# SCH_LOWCURRENT_LD293D_DRIVER_2026-05-30.net
KiCad netlist of a schematic drawn in EasyEDA
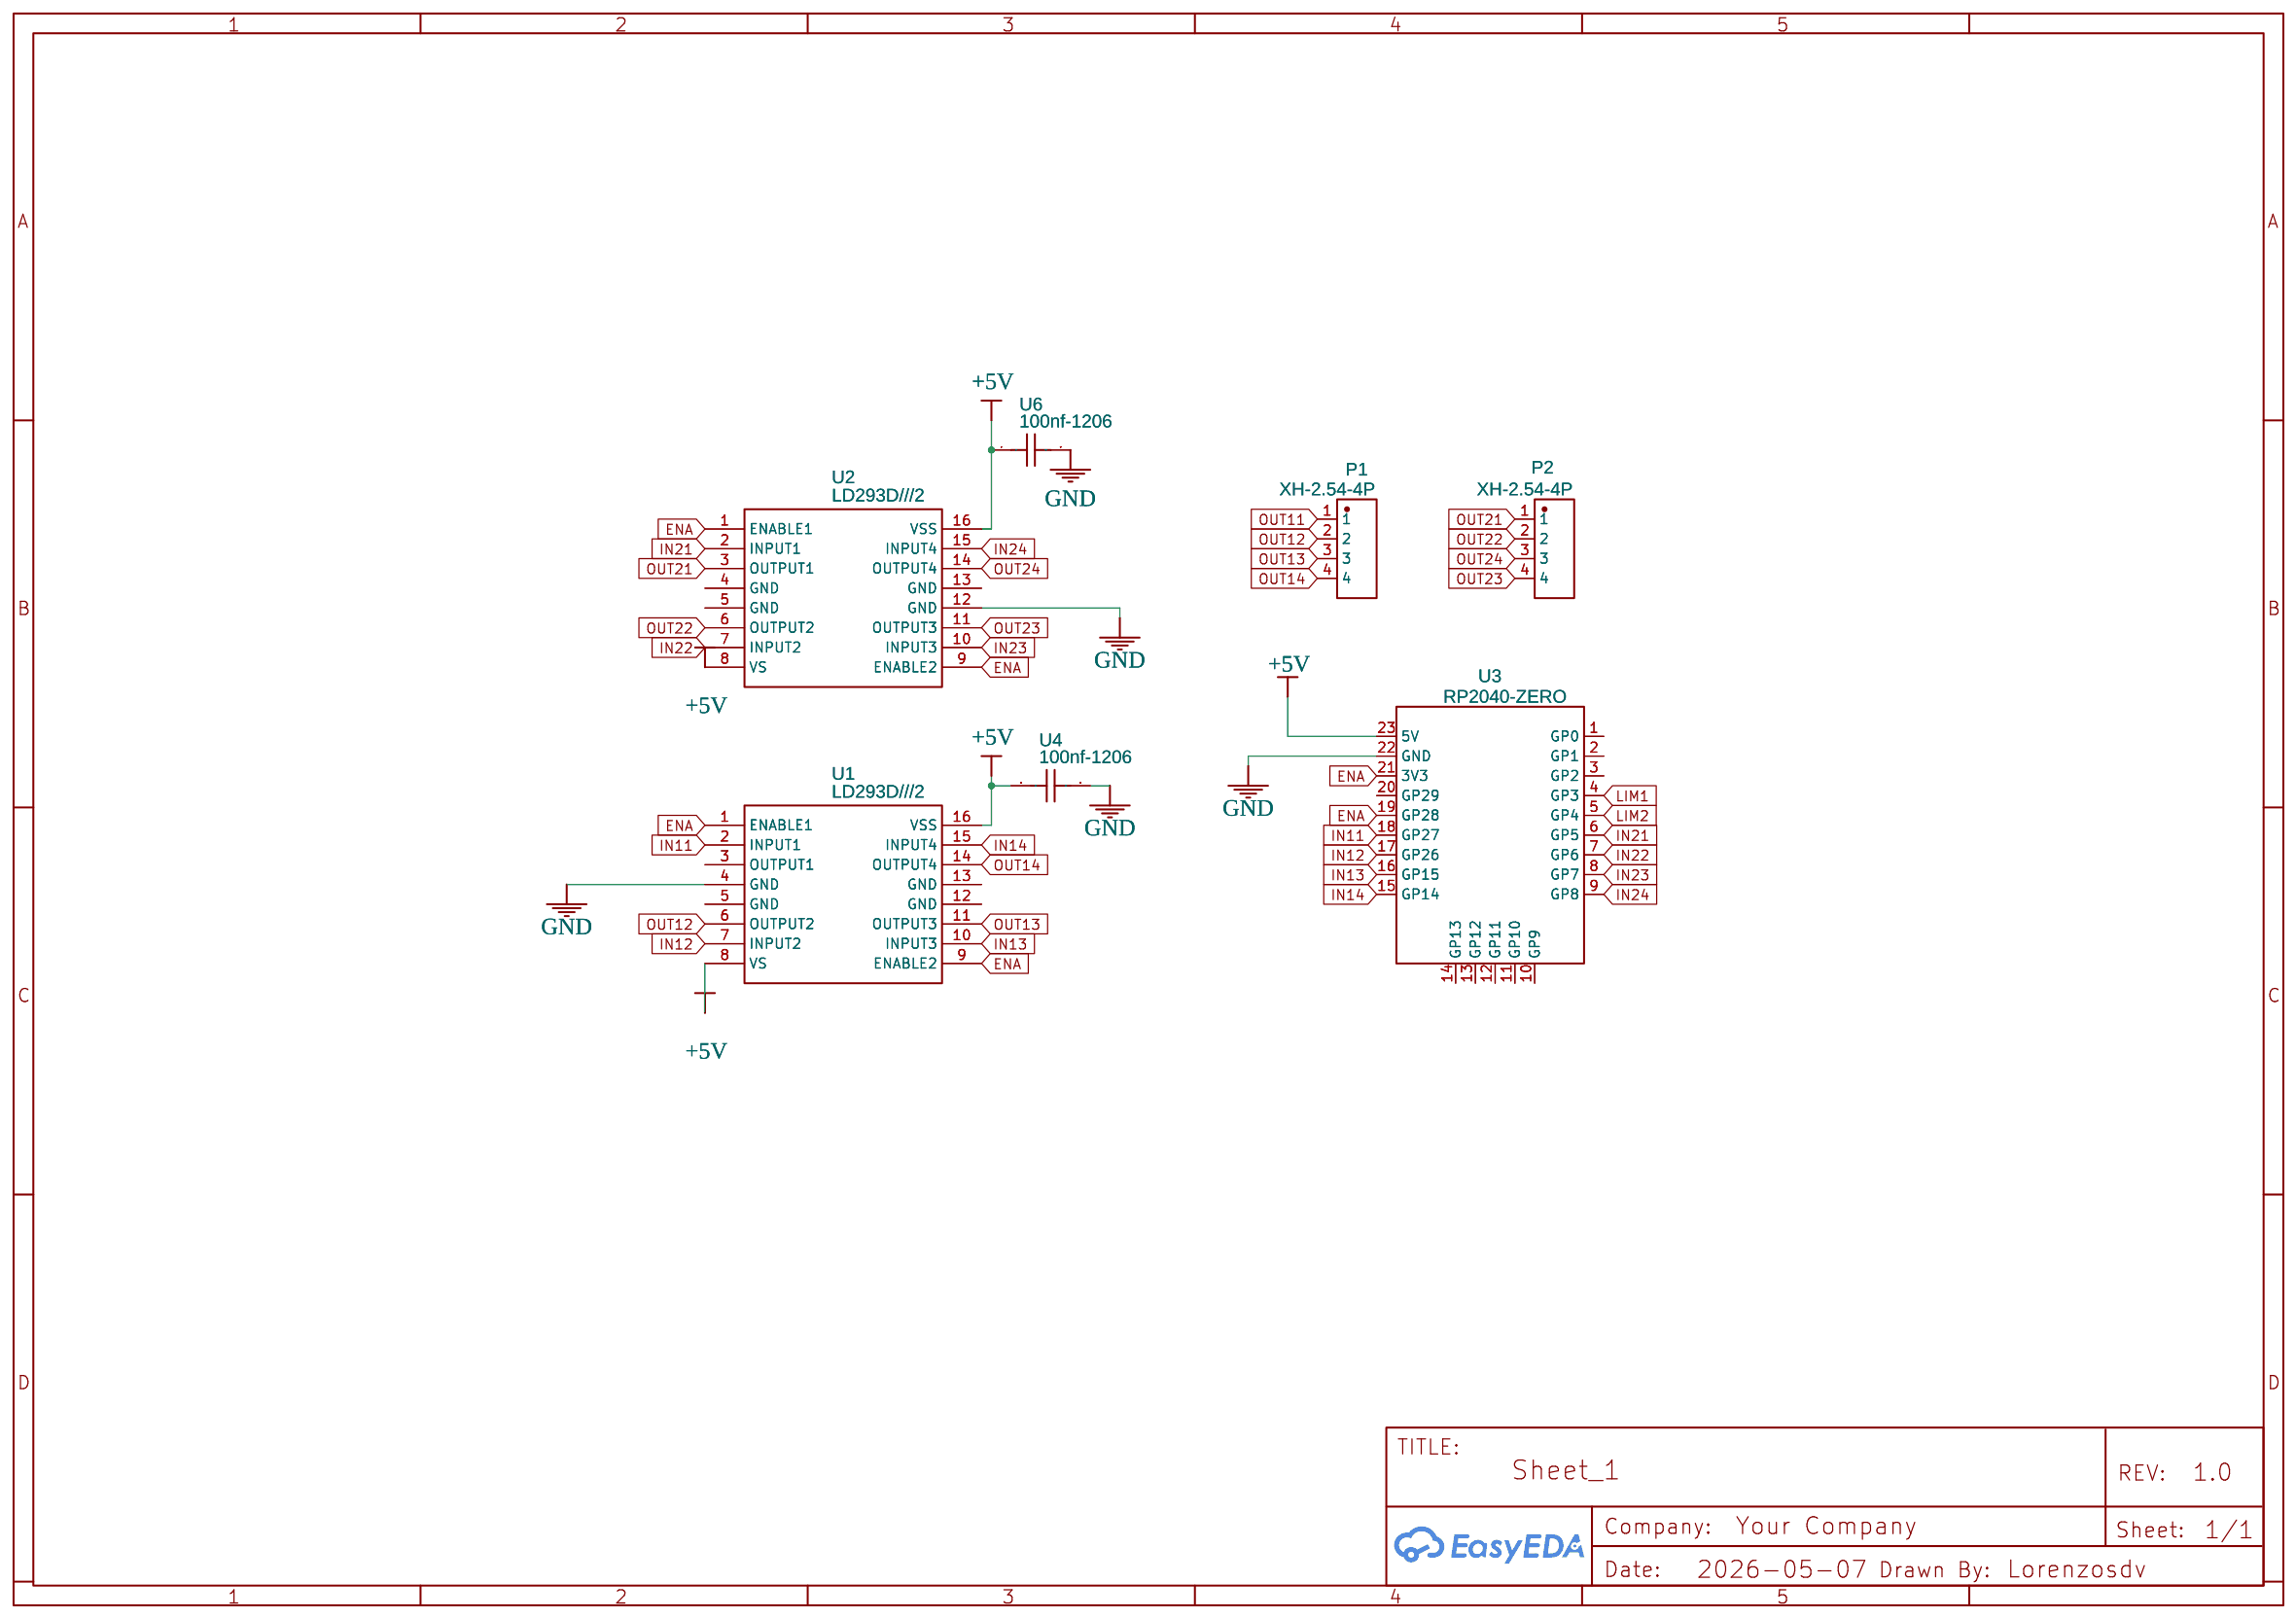
[diagram p0: schematic sheet]

(export (version "E")
  (design (tool "Eeschema 10.0.6"))
  (components
    (comp (ref "P1") (value "XH-2.54-4P") (libsource (lib "") (part "XH-2.54-4P")))
    (comp (ref "P2") (value "XH-2.54-4P") (libsource (lib "") (part "XH-2.54-4P")))
    (comp (ref "U1")
      (value "LD293D///2")
      (fields (field (name "Manufacturer Part") "L293D") (field (name "Manufacturer") "STMicroelectronics"))
      (libsource (lib "") (part "LD293D///2"))
    )
    (comp (ref "U2")
      (value "LD293D///2")
      (fields (field (name "Manufacturer Part") "L293D") (field (name "Manufacturer") "STMicroelectronics"))
      (libsource (lib "") (part "LD293D///2"))
    )
    (comp (ref "U3")
      (value "RP2040-ZERO")
      (fields
        (field (name "Manufacturer Part") "RP2040-Zero")
        (field (name "Manufacturer") "Waveshare(微雪电子)")
      )
      (libsource (lib "") (part "RP2040-ZERO"))
    )
    (comp (ref "U4")
      (value "100nf-1206")
      (fields (field (name "Manufacturer Part") "220UF-1206"))
      (libsource (lib "") (part "220UF-1206"))
    )
    (comp (ref "U6")
      (value "100nf-1206")
      (fields (field (name "Manufacturer Part") "220UF-1206"))
      (libsource (lib "") (part "220UF-1206"))
    )
  )
  (nets
    (net (code "1") (name "+5V") (class "Default")
      (node (ref "U1") (pin "16") (pinfunction "VSS_16") (pintype "unspecified"))
      (node (ref "U1") (pin "8") (pinfunction "VS_8") (pintype "unspecified"))
      (node (ref "U2") (pin "16") (pinfunction "VSS_16") (pintype "unspecified"))
      (node (ref "U2") (pin "8") (pinfunction "VS_8") (pintype "unspecified"))
      (node (ref "U3") (pin "23") (pinfunction "5V_23") (pintype "unspecified"))
      (node (ref "U4") (pin "1") (pinfunction "1_1") (pintype "unspecified"))
      (node (ref "U6") (pin "1") (pinfunction "1_1") (pintype "unspecified"))
    )
    (net (code "2") (name "ENA") (class "Default")
      (node (ref "U1") (pin "1") (pinfunction "ENABLE1_1") (pintype "unspecified"))
      (node (ref "U1") (pin "9") (pinfunction "ENABLE2_9") (pintype "unspecified"))
      (node (ref "U2") (pin "1") (pinfunction "ENABLE1_1") (pintype "unspecified"))
      (node (ref "U2") (pin "9") (pinfunction "ENABLE2_9") (pintype "unspecified"))
      (node (ref "U3") (pin "19") (pinfunction "GP28_19") (pintype "unspecified"))
      (node (ref "U3") (pin "21") (pinfunction "3V3_21") (pintype "unspecified"))
    )
    (net (code "3") (name "GND") (class "Default")
      (node (ref "U1") (pin "4") (pinfunction "GND_4") (pintype "unspecified"))
      (node (ref "U2") (pin "12") (pinfunction "GND_12") (pintype "unspecified"))
      (node (ref "U3") (pin "22") (pinfunction "GND_22") (pintype "unspecified"))
      (node (ref "U4") (pin "2") (pinfunction "2_2") (pintype "unspecified"))
      (node (ref "U6") (pin "2") (pinfunction "2_2") (pintype "unspecified"))
    )
    (net (code "4") (name "IN11") (class "Default")
      (node (ref "U1") (pin "2") (pinfunction "INPUT1_2") (pintype "unspecified"))
      (node (ref "U3") (pin "18") (pinfunction "GP27_18") (pintype "unspecified"))
    )
    (net (code "5") (name "IN12") (class "Default")
      (node (ref "U1") (pin "7") (pinfunction "INPUT2_7") (pintype "unspecified"))
      (node (ref "U3") (pin "17") (pinfunction "GP26_17") (pintype "unspecified"))
    )
    (net (code "6") (name "IN13") (class "Default")
      (node (ref "U1") (pin "10") (pinfunction "INPUT3_10") (pintype "unspecified"))
      (node (ref "U3") (pin "16") (pinfunction "GP15_16") (pintype "unspecified"))
    )
    (net (code "7") (name "IN14") (class "Default")
      (node (ref "U1") (pin "15") (pinfunction "INPUT4_15") (pintype "unspecified"))
      (node (ref "U3") (pin "15") (pinfunction "GP14_15") (pintype "unspecified"))
    )
    (net (code "8") (name "IN21") (class "Default")
      (node (ref "U2") (pin "2") (pinfunction "INPUT1_2") (pintype "unspecified"))
      (node (ref "U3") (pin "6") (pinfunction "GP5_6") (pintype "unspecified"))
    )
    (net (code "9") (name "IN22") (class "Default")
      (node (ref "U2") (pin "7") (pinfunction "INPUT2_7") (pintype "unspecified"))
      (node (ref "U3") (pin "7") (pinfunction "GP6_7") (pintype "unspecified"))
    )
    (net (code "10") (name "IN23") (class "Default")
      (node (ref "U2") (pin "10") (pinfunction "INPUT3_10") (pintype "unspecified"))
      (node (ref "U3") (pin "8") (pinfunction "GP7_8") (pintype "unspecified"))
    )
    (net (code "11") (name "IN24") (class "Default")
      (node (ref "U2") (pin "15") (pinfunction "INPUT4_15") (pintype "unspecified"))
      (node (ref "U3") (pin "9") (pinfunction "GP8_9") (pintype "unspecified"))
    )
    (net (code "12") (name "LIM1") (class "Default")
      (node (ref "U3") (pin "4") (pinfunction "GP3_4") (pintype "unspecified"))
    )
    (net (code "13") (name "LIM2") (class "Default")
      (node (ref "U3") (pin "5") (pinfunction "GP4_5") (pintype "unspecified"))
    )
    (net (code "14") (name "OUT11") (class "Default")
      (node (ref "P1") (pin "1") (pinfunction "1_1") (pintype "unspecified"))
    )
    (net (code "15") (name "OUT12") (class "Default")
      (node (ref "P1") (pin "2") (pinfunction "2_2") (pintype "unspecified"))
      (node (ref "U1") (pin "6") (pinfunction "OUTPUT2_6") (pintype "unspecified"))
    )
    (net (code "16") (name "OUT13") (class "Default")
      (node (ref "P1") (pin "3") (pinfunction "3_3") (pintype "unspecified"))
      (node (ref "U1") (pin "11") (pinfunction "OUTPUT3_11") (pintype "unspecified"))
    )
    (net (code "17") (name "OUT14") (class "Default")
      (node (ref "P1") (pin "4") (pinfunction "4_4") (pintype "unspecified"))
      (node (ref "U1") (pin "14") (pinfunction "OUTPUT4_14") (pintype "unspecified"))
    )
    (net (code "18") (name "OUT21") (class "Default")
      (node (ref "P2") (pin "1") (pinfunction "1_1") (pintype "unspecified"))
      (node (ref "U2") (pin "3") (pinfunction "OUTPUT1_3") (pintype "unspecified"))
    )
    (net (code "19") (name "OUT22") (class "Default")
      (node (ref "P2") (pin "2") (pinfunction "2_2") (pintype "unspecified"))
      (node (ref "U2") (pin "6") (pinfunction "OUTPUT2_6") (pintype "unspecified"))
    )
    (net (code "20") (name "OUT23") (class "Default")
      (node (ref "P2") (pin "4") (pinfunction "4_4") (pintype "unspecified"))
      (node (ref "U2") (pin "11") (pinfunction "OUTPUT3_11") (pintype "unspecified"))
    )
    (net (code "21") (name "OUT24") (class "Default")
      (node (ref "P2") (pin "3") (pinfunction "3_3") (pintype "unspecified"))
      (node (ref "U2") (pin "14") (pinfunction "OUTPUT4_14") (pintype "unspecified"))
    )
    (net (code "22") (name "unconnected-(U1-GND-Pad5)") (class "Default")
      (node (ref "U1") (pin "5") (pinfunction "GND_5") (pintype "unspecified"))
    )
    (net (code "23") (name "unconnected-(U1-GND-Pad12)") (class "Default")
      (node (ref "U1") (pin "12") (pinfunction "GND_12") (pintype "unspecified"))
    )
    (net (code "24") (name "unconnected-(U1-GND-Pad13)") (class "Default")
      (node (ref "U1") (pin "13") (pinfunction "GND_13") (pintype "unspecified"))
    )
    (net (code "25") (name "unconnected-(U1-OUTPUT1-Pad3)") (class "Default")
      (node (ref "U1") (pin "3") (pinfunction "OUTPUT1_3") (pintype "unspecified"))
    )
    (net (code "26") (name "unconnected-(U2-GND-Pad4)") (class "Default")
      (node (ref "U2") (pin "4") (pinfunction "GND_4") (pintype "unspecified"))
    )
    (net (code "27") (name "unconnected-(U2-GND-Pad5)") (class "Default")
      (node (ref "U2") (pin "5") (pinfunction "GND_5") (pintype "unspecified"))
    )
    (net (code "28") (name "unconnected-(U2-GND-Pad13)") (class "Default")
      (node (ref "U2") (pin "13") (pinfunction "GND_13") (pintype "unspecified"))
    )
    (net (code "29") (name "unconnected-(U3-GP0-Pad1)") (class "Default")
      (node (ref "U3") (pin "1") (pinfunction "GP0_1") (pintype "unspecified"))
    )
    (net (code "30") (name "unconnected-(U3-GP1-Pad2)") (class "Default")
      (node (ref "U3") (pin "2") (pinfunction "GP1_2") (pintype "unspecified"))
    )
    (net (code "31") (name "unconnected-(U3-GP2-Pad3)") (class "Default")
      (node (ref "U3") (pin "3") (pinfunction "GP2_3") (pintype "unspecified"))
    )
    (net (code "32") (name "unconnected-(U3-GP9-Pad10)") (class "Default")
      (node (ref "U3") (pin "10") (pinfunction "GP9_10") (pintype "unspecified"))
    )
    (net (code "33") (name "unconnected-(U3-GP10-Pad11)") (class "Default")
      (node (ref "U3") (pin "11") (pinfunction "GP10_11") (pintype "unspecified"))
    )
    (net (code "34") (name "unconnected-(U3-GP11-Pad12)") (class "Default")
      (node (ref "U3") (pin "12") (pinfunction "GP11_12") (pintype "unspecified"))
    )
    (net (code "35") (name "unconnected-(U3-GP12-Pad13)") (class "Default")
      (node (ref "U3") (pin "13") (pinfunction "GP12_13") (pintype "unspecified"))
    )
    (net (code "36") (name "unconnected-(U3-GP13-Pad14)") (class "Default")
      (node (ref "U3") (pin "14") (pinfunction "GP13_14") (pintype "unspecified"))
    )
    (net (code "37") (name "unconnected-(U3-GP29-Pad20)") (class "Default")
      (node (ref "U3") (pin "20") (pinfunction "GP29_20") (pintype "unspecified"))
    )
  )
)
